# ControlModule.net
KiCad netlist of a schematic drawn in EAGLE
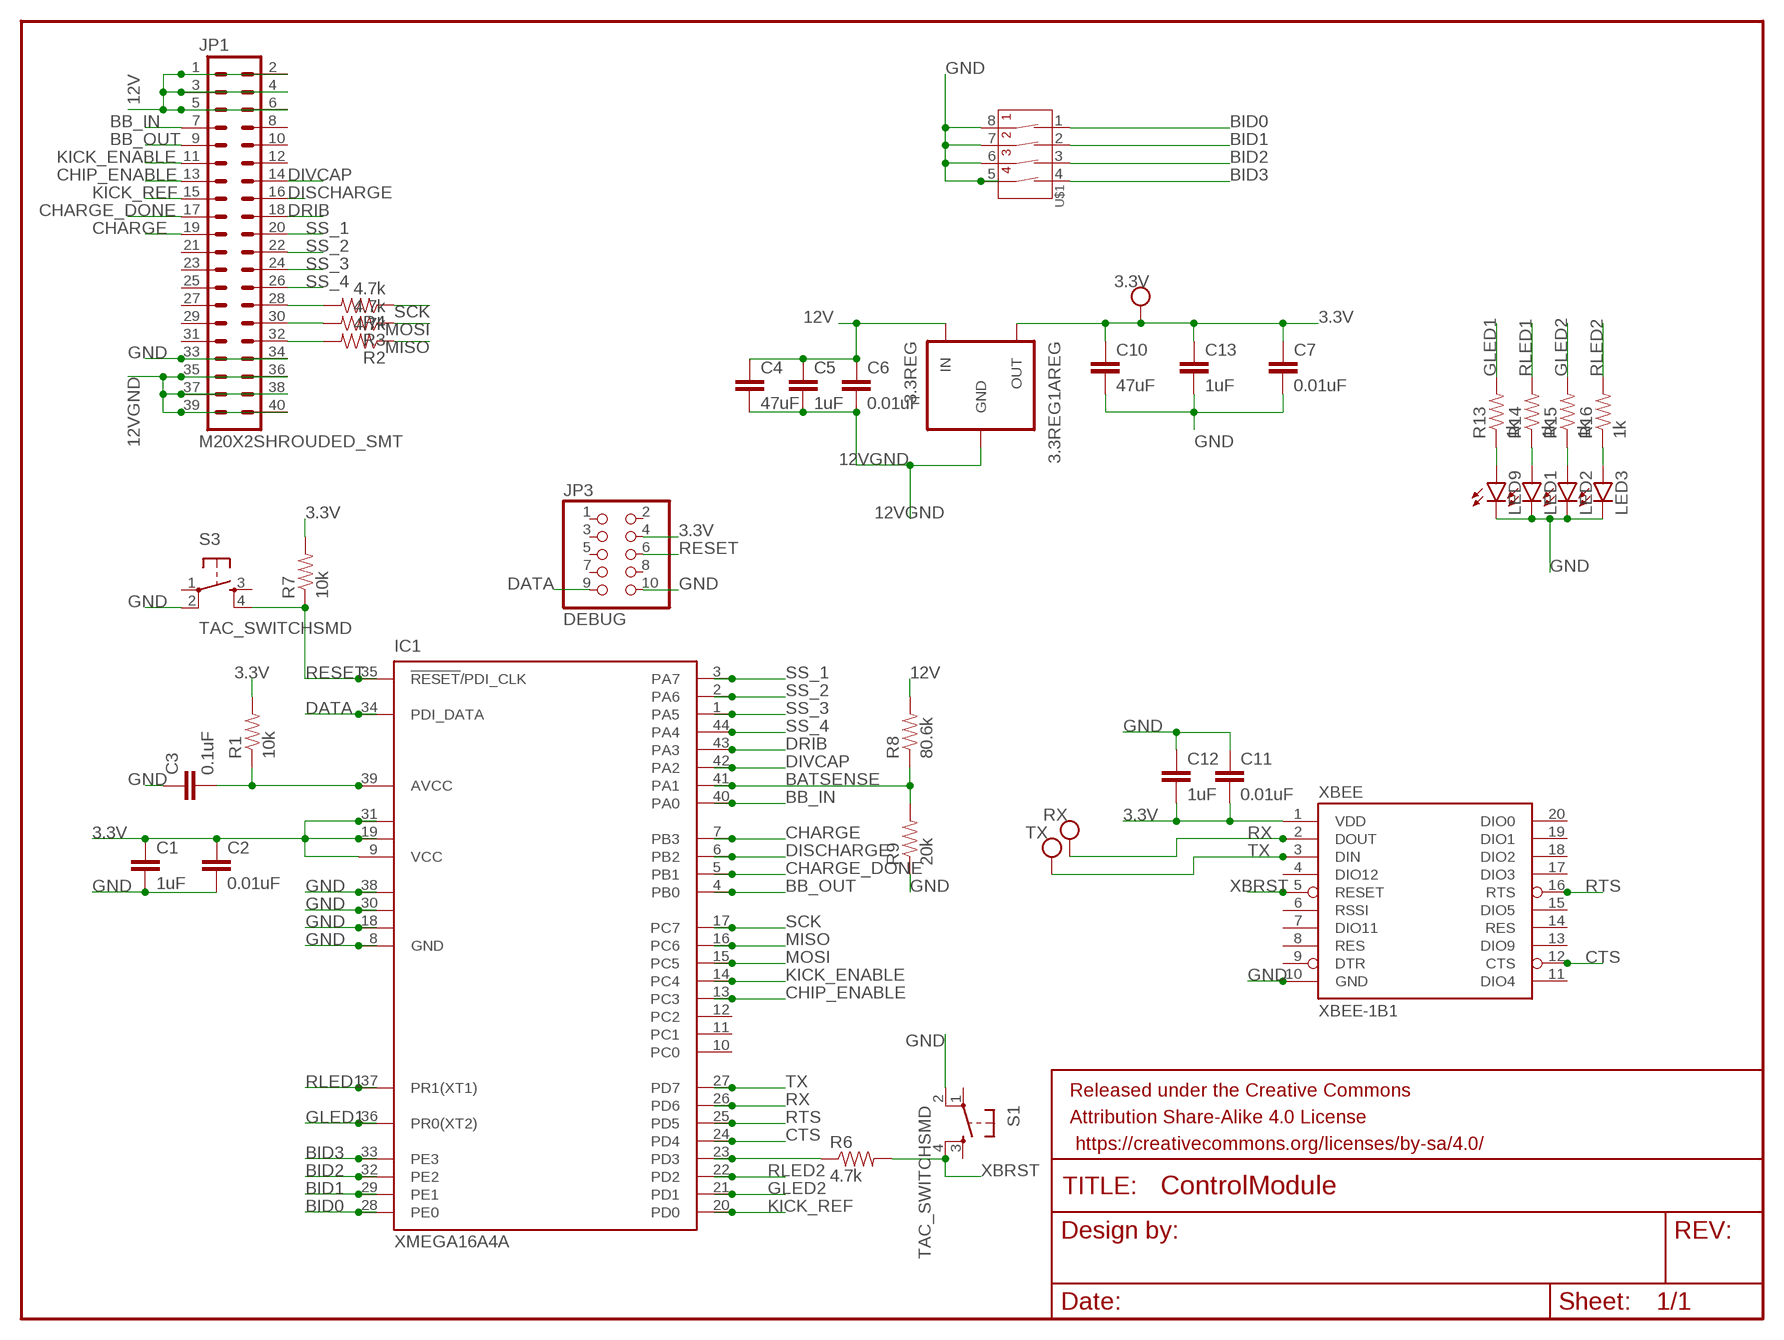
[diagram p0: schematic, sheet 1]

(export (version "E")
  (design (tool "Eeschema 10.0.6"))
  (components
    (comp (ref "3.3REG")
      (value "3.3REG1AREG")
      (footprint "eagle-import:DPAK")
      (libsource (lib "eagle-import") (part "3.3REG1AREG"))
    )
    (comp (ref "3.3V")
      (value "TEST_PT")
      (footprint "eagle-import:TESTING_PT")
      (libsource (lib "eagle-import") (part "TEST_PT"))
    )
    (comp (ref "C1")
      (value "1uF")
      (footprint "eagle-import:0805")
      (libsource (lib "eagle-import") (part "CAP0805"))
    )
    (comp (ref "C2")
      (value "0.01uF")
      (footprint "eagle-import:0805")
      (libsource (lib "eagle-import") (part "CAP0805"))
    )
    (comp (ref "C3")
      (value "0.1uF")
      (footprint "eagle-import:0805")
      (libsource (lib "eagle-import") (part "CAP0805"))
    )
    (comp (ref "C4")
      (value "47uF")
      (footprint "eagle-import:1206")
      (libsource (lib "eagle-import") (part "CAP1206"))
    )
    (comp (ref "C5")
      (value "1uF")
      (footprint "eagle-import:0805")
      (libsource (lib "eagle-import") (part "CAP0805"))
    )
    (comp (ref "C6")
      (value "0.01uF")
      (footprint "eagle-import:0805")
      (libsource (lib "eagle-import") (part "CAP0805"))
    )
    (comp (ref "C7")
      (value "0.01uF")
      (footprint "eagle-import:0805")
      (libsource (lib "eagle-import") (part "CAP0805"))
    )
    (comp (ref "C10")
      (value "47uF")
      (footprint "eagle-import:1206")
      (libsource (lib "eagle-import") (part "CAP1206"))
    )
    (comp (ref "C11")
      (value "0.01uF")
      (footprint "eagle-import:0805")
      (libsource (lib "eagle-import") (part "CAP0805"))
    )
    (comp (ref "C12")
      (value "1uF")
      (footprint "eagle-import:0805")
      (libsource (lib "eagle-import") (part "CAP0805"))
    )
    (comp (ref "C13")
      (value "1uF")
      (footprint "eagle-import:0805")
      (libsource (lib "eagle-import") (part "CAP0805"))
    )
    (comp (ref "FRAME1")
      (value "FRAME-LETTER")
      (footprint "eagle-import:CREATIVE_COMMONS")
      (libsource (lib "eagle-import") (part "FRAME-LETTER"))
    )
    (comp (ref "IC1")
      (value "XMEGA16A4A")
      (footprint "eagle-import:TQFP44")
      (libsource (lib "eagle-import") (part "XMEGA16A4A"))
    )
    (comp (ref "JP1")
      (value "M20X2SHROUDED_SMT")
      (footprint "eagle-import:2X20_SHROUDED_SMT")
      (libsource (lib "eagle-import") (part "M20X2SHROUDED_SMT"))
    )
    (comp (ref "JP3")
      (value "DEBUG")
      (footprint "eagle-import:2X05")
      (libsource (lib "eagle-import") (part "PINHD-2X5"))
    )
    (comp (ref "LED1")
      (value "LED1206")
      (footprint "eagle-import:LED-1206")
      (libsource (lib "eagle-import") (part "LED1206"))
    )
    (comp (ref "LED2")
      (value "LED1206")
      (footprint "eagle-import:LED-1206")
      (libsource (lib "eagle-import") (part "LED1206"))
    )
    (comp (ref "LED3")
      (value "LED1206")
      (footprint "eagle-import:LED-1206")
      (libsource (lib "eagle-import") (part "LED1206"))
    )
    (comp (ref "LED9")
      (value "LED1206")
      (footprint "eagle-import:LED-1206")
      (libsource (lib "eagle-import") (part "LED1206"))
    )
    (comp (ref "R1")
      (value "10k")
      (footprint "eagle-import:0805")
      (libsource (lib "eagle-import") (part "RESISTOR0805-RES"))
    )
    (comp (ref "R2")
      (value "4.7k")
      (footprint "eagle-import:0805")
      (libsource (lib "eagle-import") (part "SparkFun-Resistors_RESISTOR0805-RES"))
    )
    (comp (ref "R3")
      (value "4.7k")
      (footprint "eagle-import:0805")
      (libsource (lib "eagle-import") (part "SparkFun-Resistors_RESISTOR0805-RES"))
    )
    (comp (ref "R4")
      (value "4.7k")
      (footprint "eagle-import:0805")
      (libsource (lib "eagle-import") (part "SparkFun-Resistors_RESISTOR0805-RES"))
    )
    (comp (ref "R6")
      (value "4.7k")
      (footprint "eagle-import:0805")
      (libsource (lib "eagle-import") (part "RESISTOR0805-RES"))
    )
    (comp (ref "R7")
      (value "10k")
      (footprint "eagle-import:0805")
      (libsource (lib "eagle-import") (part "RESISTOR0805-RES"))
    )
    (comp (ref "R8")
      (value "80.6k")
      (footprint "eagle-import:0805")
      (libsource (lib "eagle-import") (part "RESISTOR0805-RES"))
    )
    (comp (ref "R9")
      (value "20k")
      (footprint "eagle-import:0805")
      (libsource (lib "eagle-import") (part "RESISTOR0805-RES"))
    )
    (comp (ref "R13")
      (value "1k")
      (footprint "eagle-import:0805")
      (libsource (lib "eagle-import") (part "RESISTOR0805-RES"))
    )
    (comp (ref "R14")
      (value "1k")
      (footprint "eagle-import:0805")
      (libsource (lib "eagle-import") (part "RESISTOR0805-RES"))
    )
    (comp (ref "R15")
      (value "1k")
      (footprint "eagle-import:0805")
      (libsource (lib "eagle-import") (part "RESISTOR0805-RES"))
    )
    (comp (ref "R16")
      (value "1k")
      (footprint "eagle-import:0805")
      (libsource (lib "eagle-import") (part "RESISTOR0805-RES"))
    )
    (comp (ref "RX")
      (value "TEST_PT")
      (footprint "eagle-import:TESTING_PT")
      (libsource (lib "eagle-import") (part "TEST_PT"))
    )
    (comp (ref "S1")
      (value "TAC_SWITCHSMD")
      (footprint "eagle-import:TACTILE-SWITCH-SMD")
      (libsource (lib "eagle-import") (part "TAC_SWITCHSMD"))
    )
    (comp (ref "S3")
      (value "TAC_SWITCHSMD")
      (footprint "eagle-import:TACTILE-SWITCH-SMD")
      (libsource (lib "eagle-import") (part "TAC_SWITCHSMD"))
    )
    (comp (ref "TX")
      (value "TEST_PT")
      (footprint "eagle-import:TESTING_PT")
      (libsource (lib "eagle-import") (part "TEST_PT"))
    )
    (comp (ref "U$1")
      (value "4-POS-DIP")
      (footprint "eagle-import:4-POS-DIP-SMD")
      (libsource (lib "eagle-import") (part "4-POS-DIP"))
    )
    (comp (ref "XBEE")
      (value "XBEE-1B1")
      (footprint "eagle-import:XBEE-1")
      (libsource (lib "eagle-import") (part "XBEE-1B1"))
    )
  )
  (nets
    (net (code "1") (name "/3.3V") (class "Default")
      (node (ref "3.3REG") (pin "SOURCE") (pinfunction "OUT_SOURCE") (pintype "bidirectional"))
      (node (ref "3.3V") (pin "P$1") (pinfunction "P$1_P$1") (pintype "bidirectional"))
      (node (ref "C1") (pin "1") (pinfunction "1_1") (pintype "passive"))
      (node (ref "C10") (pin "1") (pinfunction "1_1") (pintype "passive"))
      (node (ref "C11") (pin "2") (pinfunction "2_2") (pintype "passive"))
      (node (ref "C12") (pin "2") (pinfunction "2_2") (pintype "passive"))
      (node (ref "C13") (pin "1") (pinfunction "1_1") (pintype "passive"))
      (node (ref "C2") (pin "1") (pinfunction "1_1") (pintype "passive"))
      (node (ref "C7") (pin "1") (pinfunction "1_1") (pintype "passive"))
      (node (ref "IC1") (pin "19") (pinfunction "VCC1_19") (pintype "power_in"))
      (node (ref "IC1") (pin "31") (pinfunction "VCC2_31") (pintype "power_in"))
      (node (ref "IC1") (pin "9") (pinfunction "VCC_9") (pintype "power_in"))
      (node (ref "JP3") (pin "4") (pinfunction "4_4") (pintype "passive"))
      (node (ref "R1") (pin "2") (pinfunction "2_2") (pintype "passive"))
      (node (ref "R7") (pin "2") (pinfunction "2_2") (pintype "passive"))
      (node (ref "XBEE") (pin "1") (pinfunction "VDD_1") (pintype "power_in"))
    )
    (net (code "2") (name "/12V") (class "Default")
      (node (ref "3.3REG") (pin "GATE") (pinfunction "IN_GATE") (pintype "input"))
      (node (ref "C4") (pin "1") (pinfunction "1_1") (pintype "passive"))
      (node (ref "C5") (pin "1") (pinfunction "1_1") (pintype "passive"))
      (node (ref "C6") (pin "1") (pinfunction "1_1") (pintype "passive"))
      (node (ref "JP1") (pin "1") (pinfunction "1_1") (pintype "passive"))
      (node (ref "JP1") (pin "2") (pinfunction "2_2") (pintype "passive"))
      (node (ref "JP1") (pin "3") (pinfunction "3_3") (pintype "passive"))
      (node (ref "JP1") (pin "4") (pinfunction "4_4") (pintype "passive"))
      (node (ref "JP1") (pin "5") (pinfunction "5_5") (pintype "passive"))
      (node (ref "JP1") (pin "6") (pinfunction "6_6") (pintype "passive"))
      (node (ref "R8") (pin "2") (pinfunction "2_2") (pintype "passive"))
    )
    (net (code "3") (name "/12VGND") (class "Default")
      (node (ref "3.3REG") (pin "DRAIN") (pinfunction "GND_DRAIN") (pintype "bidirectional"))
      (node (ref "C4") (pin "2") (pinfunction "2_2") (pintype "passive"))
      (node (ref "C5") (pin "2") (pinfunction "2_2") (pintype "passive"))
      (node (ref "C6") (pin "2") (pinfunction "2_2") (pintype "passive"))
      (node (ref "JP1") (pin "35") (pinfunction "35_35") (pintype "passive"))
      (node (ref "JP1") (pin "36") (pinfunction "36_36") (pintype "passive"))
      (node (ref "JP1") (pin "37") (pinfunction "37_37") (pintype "passive"))
      (node (ref "JP1") (pin "38") (pinfunction "38_38") (pintype "passive"))
      (node (ref "JP1") (pin "39") (pinfunction "39_39") (pintype "passive"))
      (node (ref "JP1") (pin "40") (pinfunction "40_40") (pintype "passive"))
    )
    (net (code "4") (name "/BATSENSE") (class "Default")
      (node (ref "IC1") (pin "41") (pinfunction "PA1_41") (pintype "bidirectional"))
      (node (ref "R8") (pin "1") (pinfunction "1_1") (pintype "passive"))
      (node (ref "R9") (pin "2") (pinfunction "2_2") (pintype "passive"))
    )
    (net (code "5") (name "/BB_IN") (class "Default")
      (node (ref "IC1") (pin "40") (pinfunction "PA0_40") (pintype "bidirectional"))
      (node (ref "JP1") (pin "7") (pinfunction "7_7") (pintype "passive"))
    )
    (net (code "6") (name "/BB_OUT") (class "Default")
      (node (ref "IC1") (pin "4") (pinfunction "PB0_4") (pintype "bidirectional"))
      (node (ref "JP1") (pin "9") (pinfunction "9_9") (pintype "passive"))
    )
    (net (code "7") (name "/BID0") (class "Default")
      (node (ref "IC1") (pin "28") (pinfunction "PE0_28") (pintype "bidirectional"))
      (node (ref "U$1") (pin "1") (pinfunction "1A_1") (pintype "bidirectional"))
    )
    (net (code "8") (name "/BID1") (class "Default")
      (node (ref "IC1") (pin "29") (pinfunction "PE1_29") (pintype "bidirectional"))
      (node (ref "U$1") (pin "2") (pinfunction "2A_2") (pintype "bidirectional"))
    )
    (net (code "9") (name "/BID2") (class "Default")
      (node (ref "IC1") (pin "32") (pinfunction "PE2_32") (pintype "bidirectional"))
      (node (ref "U$1") (pin "3") (pinfunction "3A_3") (pintype "bidirectional"))
    )
    (net (code "10") (name "/BID3") (class "Default")
      (node (ref "IC1") (pin "33") (pinfunction "PE3_33") (pintype "bidirectional"))
      (node (ref "U$1") (pin "4") (pinfunction "4A_4") (pintype "bidirectional"))
    )
    (net (code "11") (name "/CHARGE") (class "Default")
      (node (ref "IC1") (pin "7") (pinfunction "PB3_7") (pintype "bidirectional"))
      (node (ref "JP1") (pin "19") (pinfunction "19_19") (pintype "passive"))
    )
    (net (code "12") (name "/CHARGE_DONE") (class "Default")
      (node (ref "IC1") (pin "5") (pinfunction "PB1_5") (pintype "bidirectional"))
      (node (ref "JP1") (pin "17") (pinfunction "17_17") (pintype "passive"))
    )
    (net (code "13") (name "/CHIP_ENABLE") (class "Default")
      (node (ref "IC1") (pin "13") (pinfunction "PC3_13") (pintype "bidirectional"))
      (node (ref "JP1") (pin "13") (pinfunction "13_13") (pintype "passive"))
    )
    (net (code "14") (name "/CTS") (class "Default")
      (node (ref "IC1") (pin "24") (pinfunction "PD4_24") (pintype "bidirectional"))
      (node (ref "XBEE") (pin "12") (pinfunction "CTS_12") (pintype "output"))
    )
    (net (code "15") (name "/DATA") (class "Default")
      (node (ref "IC1") (pin "34") (pinfunction "PDI_DATA_34") (pintype "bidirectional"))
      (node (ref "JP3") (pin "9") (pinfunction "9_9") (pintype "passive"))
    )
    (net (code "16") (name "/DISCHARGE") (class "Default")
      (node (ref "IC1") (pin "6") (pinfunction "PB2_6") (pintype "bidirectional"))
      (node (ref "JP1") (pin "16") (pinfunction "16_16") (pintype "passive"))
    )
    (net (code "17") (name "/DIVCAP") (class "Default")
      (node (ref "IC1") (pin "42") (pinfunction "PA2_42") (pintype "bidirectional"))
      (node (ref "JP1") (pin "14") (pinfunction "14_14") (pintype "passive"))
    )
    (net (code "18") (name "/DRIB") (class "Default")
      (node (ref "IC1") (pin "43") (pinfunction "PA3_43") (pintype "bidirectional"))
      (node (ref "JP1") (pin "18") (pinfunction "18_18") (pintype "passive"))
    )
    (net (code "19") (name "/GLED1") (class "Default")
      (node (ref "IC1") (pin "36") (pinfunction "PR0(XT2)_36") (pintype "bidirectional"))
      (node (ref "R13") (pin "2") (pinfunction "2_2") (pintype "passive"))
    )
    (net (code "20") (name "/GLED2") (class "Default")
      (node (ref "IC1") (pin "21") (pinfunction "PD1_21") (pintype "bidirectional"))
      (node (ref "R15") (pin "2") (pinfunction "2_2") (pintype "passive"))
    )
    (net (code "21") (name "/GND") (class "Default")
      (node (ref "C1") (pin "2") (pinfunction "2_2") (pintype "passive"))
      (node (ref "C10") (pin "2") (pinfunction "2_2") (pintype "passive"))
      (node (ref "C11") (pin "1") (pinfunction "1_1") (pintype "passive"))
      (node (ref "C12") (pin "1") (pinfunction "1_1") (pintype "passive"))
      (node (ref "C13") (pin "2") (pinfunction "2_2") (pintype "passive"))
      (node (ref "C2") (pin "2") (pinfunction "2_2") (pintype "passive"))
      (node (ref "C3") (pin "1") (pinfunction "1_1") (pintype "passive"))
      (node (ref "C7") (pin "2") (pinfunction "2_2") (pintype "passive"))
      (node (ref "IC1") (pin "18") (pinfunction "GND1_18") (pintype "power_in"))
      (node (ref "IC1") (pin "30") (pinfunction "GND2_30") (pintype "power_in"))
      (node (ref "IC1") (pin "38") (pinfunction "GND3_38") (pintype "power_in"))
      (node (ref "IC1") (pin "8") (pinfunction "GND_8") (pintype "power_in"))
      (node (ref "JP1") (pin "33") (pinfunction "33_33") (pintype "passive"))
      (node (ref "JP1") (pin "34") (pinfunction "34_34") (pintype "passive"))
      (node (ref "JP3") (pin "10") (pinfunction "10_10") (pintype "passive"))
      (node (ref "LED1") (pin "C") (pinfunction "C_C") (pintype "passive"))
      (node (ref "LED2") (pin "C") (pinfunction "C_C") (pintype "passive"))
      (node (ref "LED3") (pin "C") (pinfunction "C_C") (pintype "passive"))
      (node (ref "LED9") (pin "C") (pinfunction "C_C") (pintype "passive"))
      (node (ref "R9") (pin "1") (pinfunction "1_1") (pintype "passive"))
      (node (ref "S1") (pin "2") (pinfunction "2_2") (pintype "passive"))
      (node (ref "S3") (pin "2") (pinfunction "2_2") (pintype "passive"))
      (node (ref "U$1") (pin "5") (pinfunction "4B_5") (pintype "bidirectional"))
      (node (ref "U$1") (pin "6") (pinfunction "3B_6") (pintype "bidirectional"))
      (node (ref "U$1") (pin "7") (pinfunction "2B_7") (pintype "bidirectional"))
      (node (ref "U$1") (pin "8") (pinfunction "1B_8") (pintype "bidirectional"))
      (node (ref "XBEE") (pin "10") (pinfunction "GND_10") (pintype "power_in"))
    )
    (net (code "22") (name "/KICK_ENABLE") (class "Default")
      (node (ref "IC1") (pin "14") (pinfunction "PC4_14") (pintype "bidirectional"))
      (node (ref "JP1") (pin "11") (pinfunction "11_11") (pintype "passive"))
    )
    (net (code "23") (name "/KICK_REF") (class "Default")
      (node (ref "IC1") (pin "20") (pinfunction "PD0_20") (pintype "bidirectional"))
      (node (ref "JP1") (pin "15") (pinfunction "15_15") (pintype "passive"))
    )
    (net (code "24") (name "/MISO") (class "Default")
      (node (ref "IC1") (pin "16") (pinfunction "PC6_16") (pintype "bidirectional"))
      (node (ref "R2") (pin "1") (pinfunction "1_1") (pintype "passive"))
    )
    (net (code "25") (name "/MOSI") (class "Default")
      (node (ref "IC1") (pin "15") (pinfunction "PC5_15") (pintype "bidirectional"))
      (node (ref "R3") (pin "1") (pinfunction "1_1") (pintype "passive"))
    )
    (net (code "26") (name "/RESET") (class "Default")
      (node (ref "IC1") (pin "35") (pinfunction "~{RESET}/PDI_CLK_35") (pintype "bidirectional"))
      (node (ref "JP3") (pin "6") (pinfunction "6_6") (pintype "passive"))
      (node (ref "R7") (pin "1") (pinfunction "1_1") (pintype "passive"))
      (node (ref "S3") (pin "4") (pinfunction "4_4") (pintype "passive"))
    )
    (net (code "27") (name "/RLED1") (class "Default")
      (node (ref "IC1") (pin "37") (pinfunction "PR1(XT1)_37") (pintype "bidirectional"))
      (node (ref "R14") (pin "2") (pinfunction "2_2") (pintype "passive"))
    )
    (net (code "28") (name "/RLED2") (class "Default")
      (node (ref "IC1") (pin "22") (pinfunction "PD2_22") (pintype "bidirectional"))
      (node (ref "R16") (pin "2") (pinfunction "2_2") (pintype "passive"))
    )
    (net (code "29") (name "/RTS") (class "Default")
      (node (ref "IC1") (pin "25") (pinfunction "PD5_25") (pintype "bidirectional"))
      (node (ref "XBEE") (pin "16") (pinfunction "RTS_16") (pintype "input"))
    )
    (net (code "30") (name "/RX") (class "Default")
      (node (ref "IC1") (pin "26") (pinfunction "PD6_26") (pintype "bidirectional"))
      (node (ref "RX") (pin "P$1") (pinfunction "P$1_P$1") (pintype "bidirectional"))
      (node (ref "XBEE") (pin "2") (pinfunction "DOUT_2") (pintype "output"))
    )
    (net (code "31") (name "/SCK") (class "Default")
      (node (ref "IC1") (pin "17") (pinfunction "PC7_17") (pintype "bidirectional"))
      (node (ref "R4") (pin "1") (pinfunction "1_1") (pintype "passive"))
    )
    (net (code "32") (name "/SS_1") (class "Default")
      (node (ref "IC1") (pin "3") (pinfunction "PA7_3") (pintype "bidirectional"))
      (node (ref "JP1") (pin "20") (pinfunction "20_20") (pintype "passive"))
    )
    (net (code "33") (name "/SS_2") (class "Default")
      (node (ref "IC1") (pin "2") (pinfunction "PA6_2") (pintype "bidirectional"))
      (node (ref "JP1") (pin "22") (pinfunction "22_22") (pintype "passive"))
    )
    (net (code "34") (name "/SS_3") (class "Default")
      (node (ref "IC1") (pin "1") (pinfunction "PA5_1") (pintype "bidirectional"))
      (node (ref "JP1") (pin "24") (pinfunction "24_24") (pintype "passive"))
    )
    (net (code "35") (name "/SS_4") (class "Default")
      (node (ref "IC1") (pin "44") (pinfunction "PA4_44") (pintype "bidirectional"))
      (node (ref "JP1") (pin "26") (pinfunction "26_26") (pintype "passive"))
    )
    (net (code "36") (name "/TX") (class "Default")
      (node (ref "IC1") (pin "27") (pinfunction "PD7_27") (pintype "bidirectional"))
      (node (ref "TX") (pin "P$1") (pinfunction "P$1_P$1") (pintype "bidirectional"))
      (node (ref "XBEE") (pin "3") (pinfunction "DIN_3") (pintype "input"))
    )
    (net (code "37") (name "/XBRST") (class "Default")
      (node (ref "R6") (pin "2") (pinfunction "2_2") (pintype "passive"))
      (node (ref "S1") (pin "4") (pinfunction "4_4") (pintype "passive"))
      (node (ref "XBEE") (pin "5") (pinfunction "RESET_5") (pintype "input"))
    )
    (net (code "38") (name "Net-(IC1-AVCC)") (class "Default")
      (node (ref "C3") (pin "2") (pinfunction "2_2") (pintype "passive"))
      (node (ref "IC1") (pin "39") (pinfunction "AVCC_39") (pintype "power_in"))
      (node (ref "R1") (pin "1") (pinfunction "1_1") (pintype "passive"))
    )
    (net (code "39") (name "Net-(IC1-PD3)") (class "Default")
      (node (ref "IC1") (pin "23") (pinfunction "PD3_23") (pintype "bidirectional"))
      (node (ref "R6") (pin "1") (pinfunction "1_1") (pintype "passive"))
    )
    (net (code "40") (name "Net-(JP1-Pad28)") (class "Default")
      (node (ref "JP1") (pin "28") (pinfunction "28_28") (pintype "passive"))
      (node (ref "R4") (pin "2") (pinfunction "2_2") (pintype "passive"))
    )
    (net (code "41") (name "Net-(JP1-Pad30)") (class "Default")
      (node (ref "JP1") (pin "30") (pinfunction "30_30") (pintype "passive"))
      (node (ref "R3") (pin "2") (pinfunction "2_2") (pintype "passive"))
    )
    (net (code "42") (name "Net-(JP1-Pad32)") (class "Default")
      (node (ref "JP1") (pin "32") (pinfunction "32_32") (pintype "passive"))
      (node (ref "R2") (pin "2") (pinfunction "2_2") (pintype "passive"))
    )
    (net (code "43") (name "Net-(LED1-PadA)") (class "Default")
      (node (ref "LED1") (pin "A") (pinfunction "A_A") (pintype "passive"))
      (node (ref "R14") (pin "1") (pinfunction "1_1") (pintype "passive"))
    )
    (net (code "44") (name "Net-(LED2-PadA)") (class "Default")
      (node (ref "LED2") (pin "A") (pinfunction "A_A") (pintype "passive"))
      (node (ref "R15") (pin "1") (pinfunction "1_1") (pintype "passive"))
    )
    (net (code "45") (name "Net-(LED3-PadA)") (class "Default")
      (node (ref "LED3") (pin "A") (pinfunction "A_A") (pintype "passive"))
      (node (ref "R16") (pin "1") (pinfunction "1_1") (pintype "passive"))
    )
    (net (code "46") (name "Net-(LED9-PadA)") (class "Default")
      (node (ref "LED9") (pin "A") (pinfunction "A_A") (pintype "passive"))
      (node (ref "R13") (pin "1") (pinfunction "1_1") (pintype "passive"))
    )
    (net (code "47") (name "unconnected-(IC1-PC0-Pad10)") (class "Default")
      (node (ref "IC1") (pin "10") (pinfunction "PC0_10") (pintype "bidirectional"))
    )
    (net (code "48") (name "unconnected-(IC1-PC1-Pad11)") (class "Default")
      (node (ref "IC1") (pin "11") (pinfunction "PC1_11") (pintype "bidirectional"))
    )
    (net (code "49") (name "unconnected-(IC1-PC2-Pad12)") (class "Default")
      (node (ref "IC1") (pin "12") (pinfunction "PC2_12") (pintype "bidirectional"))
    )
    (net (code "50") (name "unconnected-(JP1-Pad8)") (class "Default")
      (node (ref "JP1") (pin "8") (pinfunction "8_8") (pintype "passive"))
    )
    (net (code "51") (name "unconnected-(JP1-Pad10)") (class "Default")
      (node (ref "JP1") (pin "10") (pinfunction "10_10") (pintype "passive"))
    )
    (net (code "52") (name "unconnected-(JP1-Pad12)") (class "Default")
      (node (ref "JP1") (pin "12") (pinfunction "12_12") (pintype "passive"))
    )
    (net (code "53") (name "unconnected-(JP1-Pad21)") (class "Default")
      (node (ref "JP1") (pin "21") (pinfunction "21_21") (pintype "passive"))
    )
    (net (code "54") (name "unconnected-(JP1-Pad23)") (class "Default")
      (node (ref "JP1") (pin "23") (pinfunction "23_23") (pintype "passive"))
    )
    (net (code "55") (name "unconnected-(JP1-Pad25)") (class "Default")
      (node (ref "JP1") (pin "25") (pinfunction "25_25") (pintype "passive"))
    )
    (net (code "56") (name "unconnected-(JP1-Pad27)") (class "Default")
      (node (ref "JP1") (pin "27") (pinfunction "27_27") (pintype "passive"))
    )
    (net (code "57") (name "unconnected-(JP1-Pad29)") (class "Default")
      (node (ref "JP1") (pin "29") (pinfunction "29_29") (pintype "passive"))
    )
    (net (code "58") (name "unconnected-(JP1-Pad31)") (class "Default")
      (node (ref "JP1") (pin "31") (pinfunction "31_31") (pintype "passive"))
    )
    (net (code "59") (name "unconnected-(JP3-Pad1)") (class "Default")
      (node (ref "JP3") (pin "1") (pinfunction "1_1") (pintype "passive"))
    )
    (net (code "60") (name "unconnected-(JP3-Pad2)") (class "Default")
      (node (ref "JP3") (pin "2") (pinfunction "2_2") (pintype "passive"))
    )
    (net (code "61") (name "unconnected-(JP3-Pad3)") (class "Default")
      (node (ref "JP3") (pin "3") (pinfunction "3_3") (pintype "passive"))
    )
    (net (code "62") (name "unconnected-(JP3-Pad5)") (class "Default")
      (node (ref "JP3") (pin "5") (pinfunction "5_5") (pintype "passive"))
    )
    (net (code "63") (name "unconnected-(JP3-Pad7)") (class "Default")
      (node (ref "JP3") (pin "7") (pinfunction "7_7") (pintype "passive"))
    )
    (net (code "64") (name "unconnected-(JP3-Pad8)") (class "Default")
      (node (ref "JP3") (pin "8") (pinfunction "8_8") (pintype "passive"))
    )
    (net (code "65") (name "unconnected-(S1-Pad1)") (class "Default")
      (node (ref "S1") (pin "1") (pinfunction "1_1") (pintype "passive"))
    )
    (net (code "66") (name "unconnected-(S1-Pad3)") (class "Default")
      (node (ref "S1") (pin "3") (pinfunction "3_3") (pintype "passive"))
    )
    (net (code "67") (name "unconnected-(S3-Pad1)") (class "Default")
      (node (ref "S3") (pin "1") (pinfunction "1_1") (pintype "passive"))
    )
    (net (code "68") (name "unconnected-(S3-Pad3)") (class "Default")
      (node (ref "S3") (pin "3") (pinfunction "3_3") (pintype "passive"))
    )
    (net (code "69") (name "unconnected-(XBEE-DIO0-Pad20)") (class "Default")
      (node (ref "XBEE") (pin "20") (pinfunction "DIO0_20") (pintype "bidirectional"))
    )
    (net (code "70") (name "unconnected-(XBEE-DIO1-Pad19)") (class "Default")
      (node (ref "XBEE") (pin "19") (pinfunction "DIO1_19") (pintype "bidirectional"))
    )
    (net (code "71") (name "unconnected-(XBEE-DIO2-Pad18)") (class "Default")
      (node (ref "XBEE") (pin "18") (pinfunction "DIO2_18") (pintype "bidirectional"))
    )
    (net (code "72") (name "unconnected-(XBEE-DIO3-Pad17)") (class "Default")
      (node (ref "XBEE") (pin "17") (pinfunction "DIO3_17") (pintype "bidirectional"))
    )
    (net (code "73") (name "unconnected-(XBEE-DIO4-Pad11)") (class "Default")
      (node (ref "XBEE") (pin "11") (pinfunction "DIO4_11") (pintype "bidirectional"))
    )
    (net (code "74") (name "unconnected-(XBEE-DIO5-Pad15)") (class "Default")
      (node (ref "XBEE") (pin "15") (pinfunction "DIO5_15") (pintype "bidirectional"))
    )
    (net (code "75") (name "unconnected-(XBEE-DIO9-Pad13)") (class "Default")
      (node (ref "XBEE") (pin "13") (pinfunction "DIO9_13") (pintype "bidirectional"))
    )
    (net (code "76") (name "unconnected-(XBEE-DIO11-Pad7)") (class "Default")
      (node (ref "XBEE") (pin "7") (pinfunction "DIO11_7") (pintype "bidirectional"))
    )
    (net (code "77") (name "unconnected-(XBEE-DIO12-Pad4)") (class "Default")
      (node (ref "XBEE") (pin "4") (pinfunction "DIO12_4") (pintype "bidirectional"))
    )
    (net (code "78") (name "unconnected-(XBEE-DTR-Pad9)") (class "Default")
      (node (ref "XBEE") (pin "9") (pinfunction "DTR_9") (pintype "bidirectional"))
    )
    (net (code "79") (name "unconnected-(XBEE-RES-Pad8)") (class "Default")
      (node (ref "XBEE") (pin "8") (pinfunction "RES_8") (pintype "bidirectional"))
    )
    (net (code "80") (name "unconnected-(XBEE-RES-Pad14)") (class "Default")
      (node (ref "XBEE") (pin "14") (pinfunction "RES_14") (pintype "bidirectional"))
    )
    (net (code "81") (name "unconnected-(XBEE-RSSI-Pad6)") (class "Default")
      (node (ref "XBEE") (pin "6") (pinfunction "RSSI_6") (pintype "bidirectional"))
    )
  )
)
